# STM32F05_V2.net
KiCad netlist of a schematic drawn in EAGLE
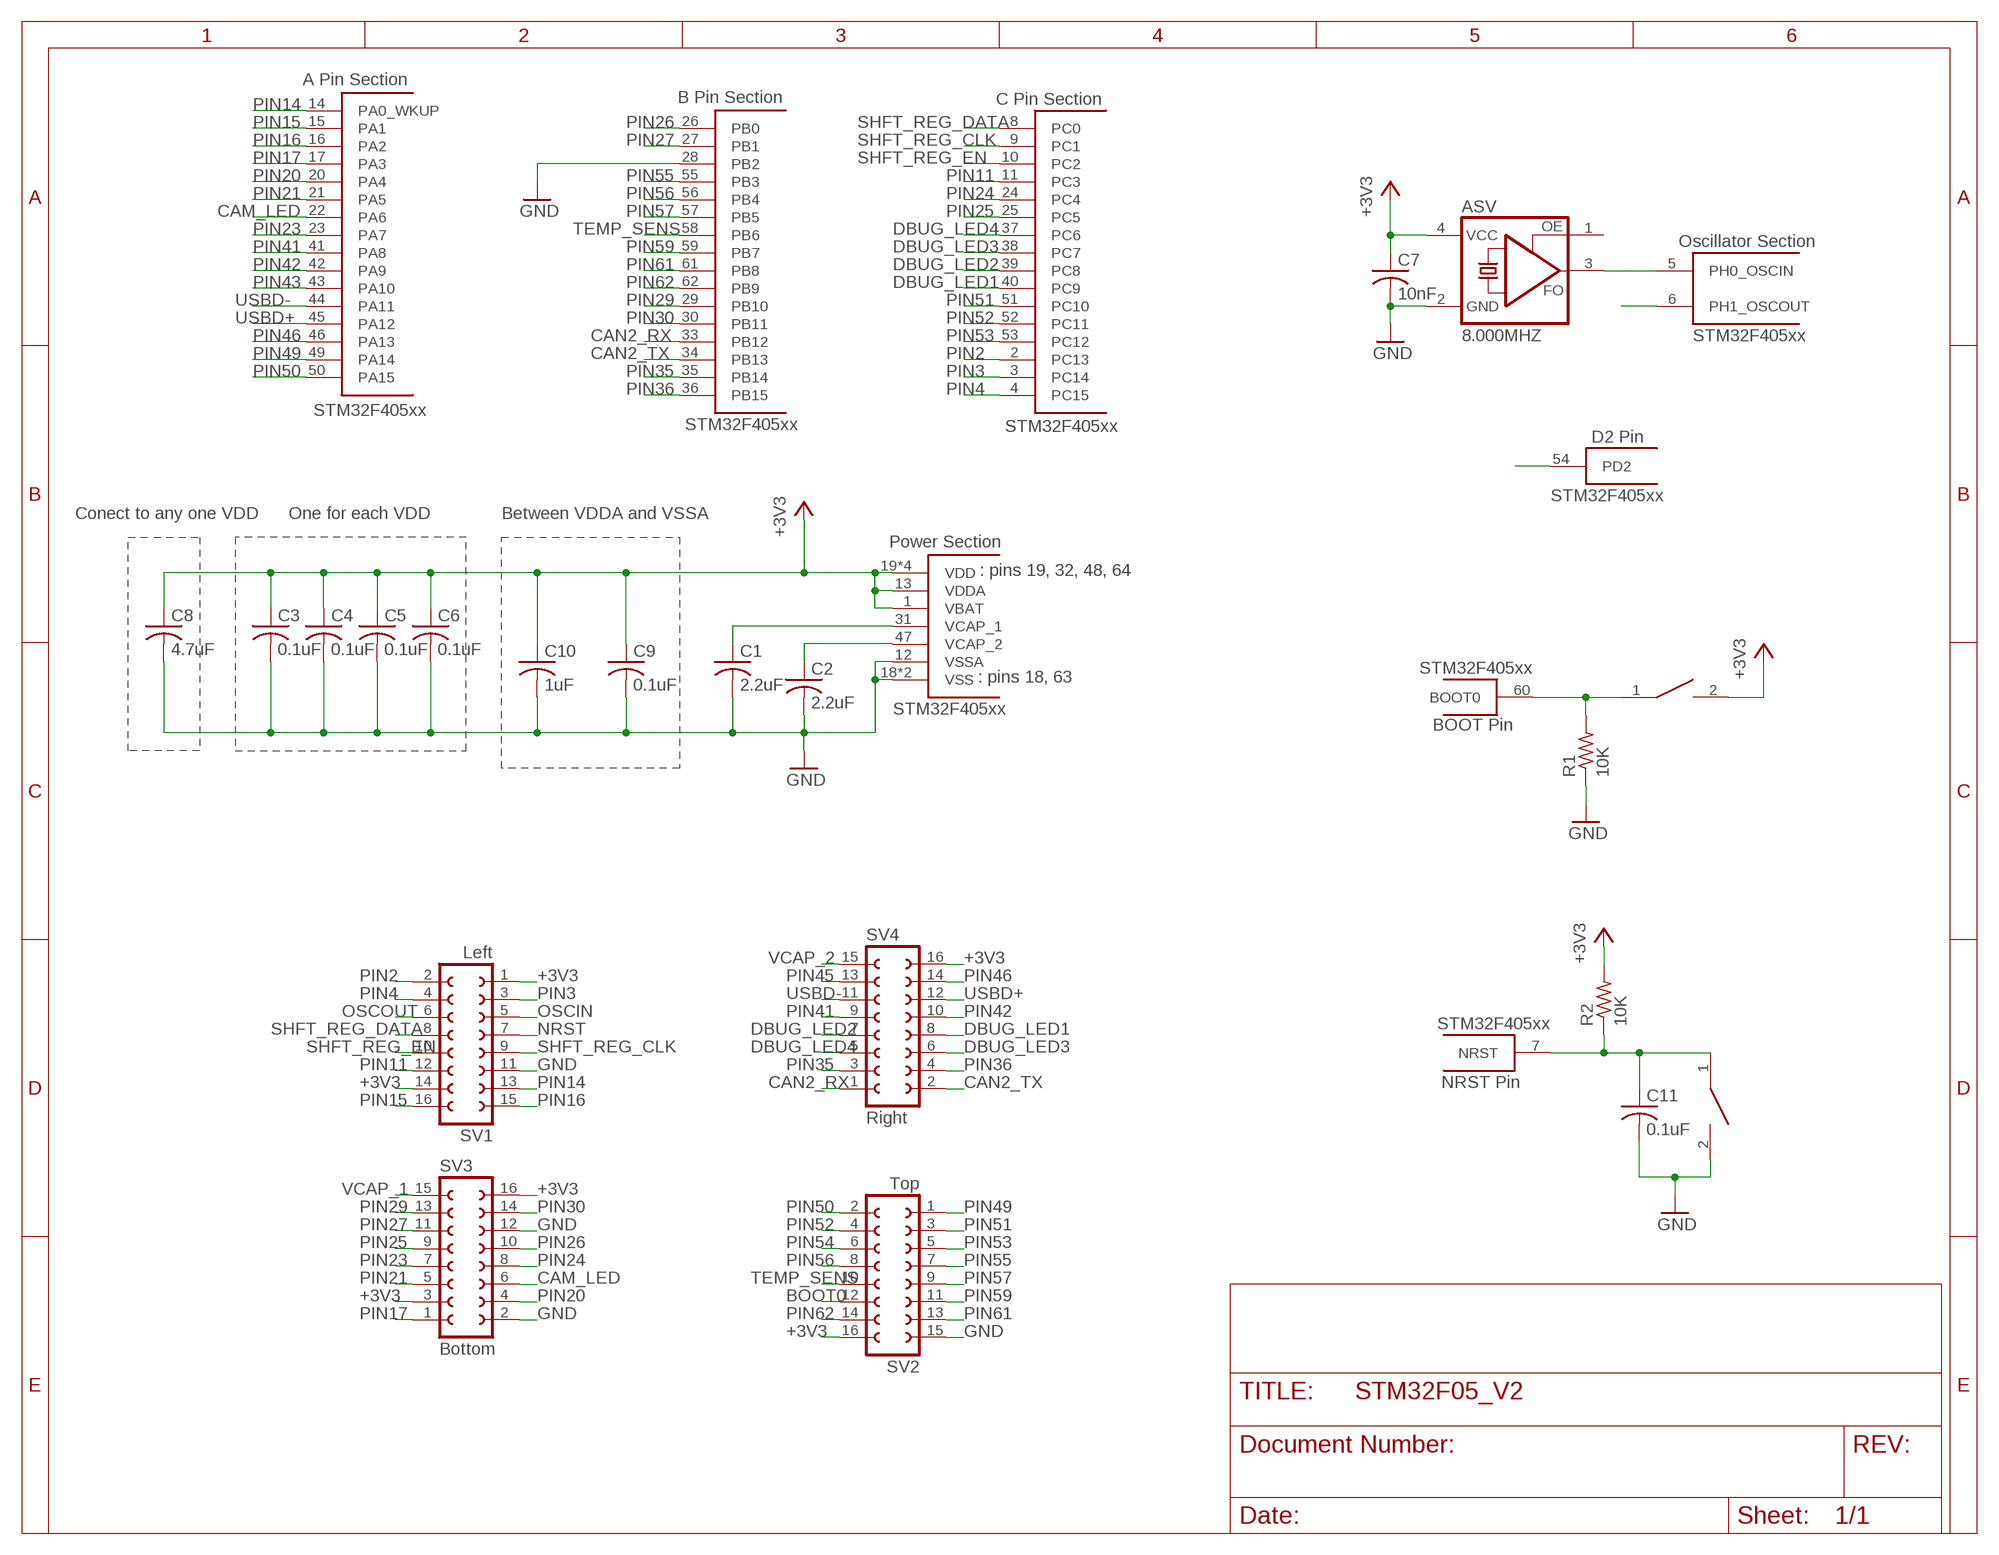
[diagram p0: schematic, sheet 1, part 1 of 2]
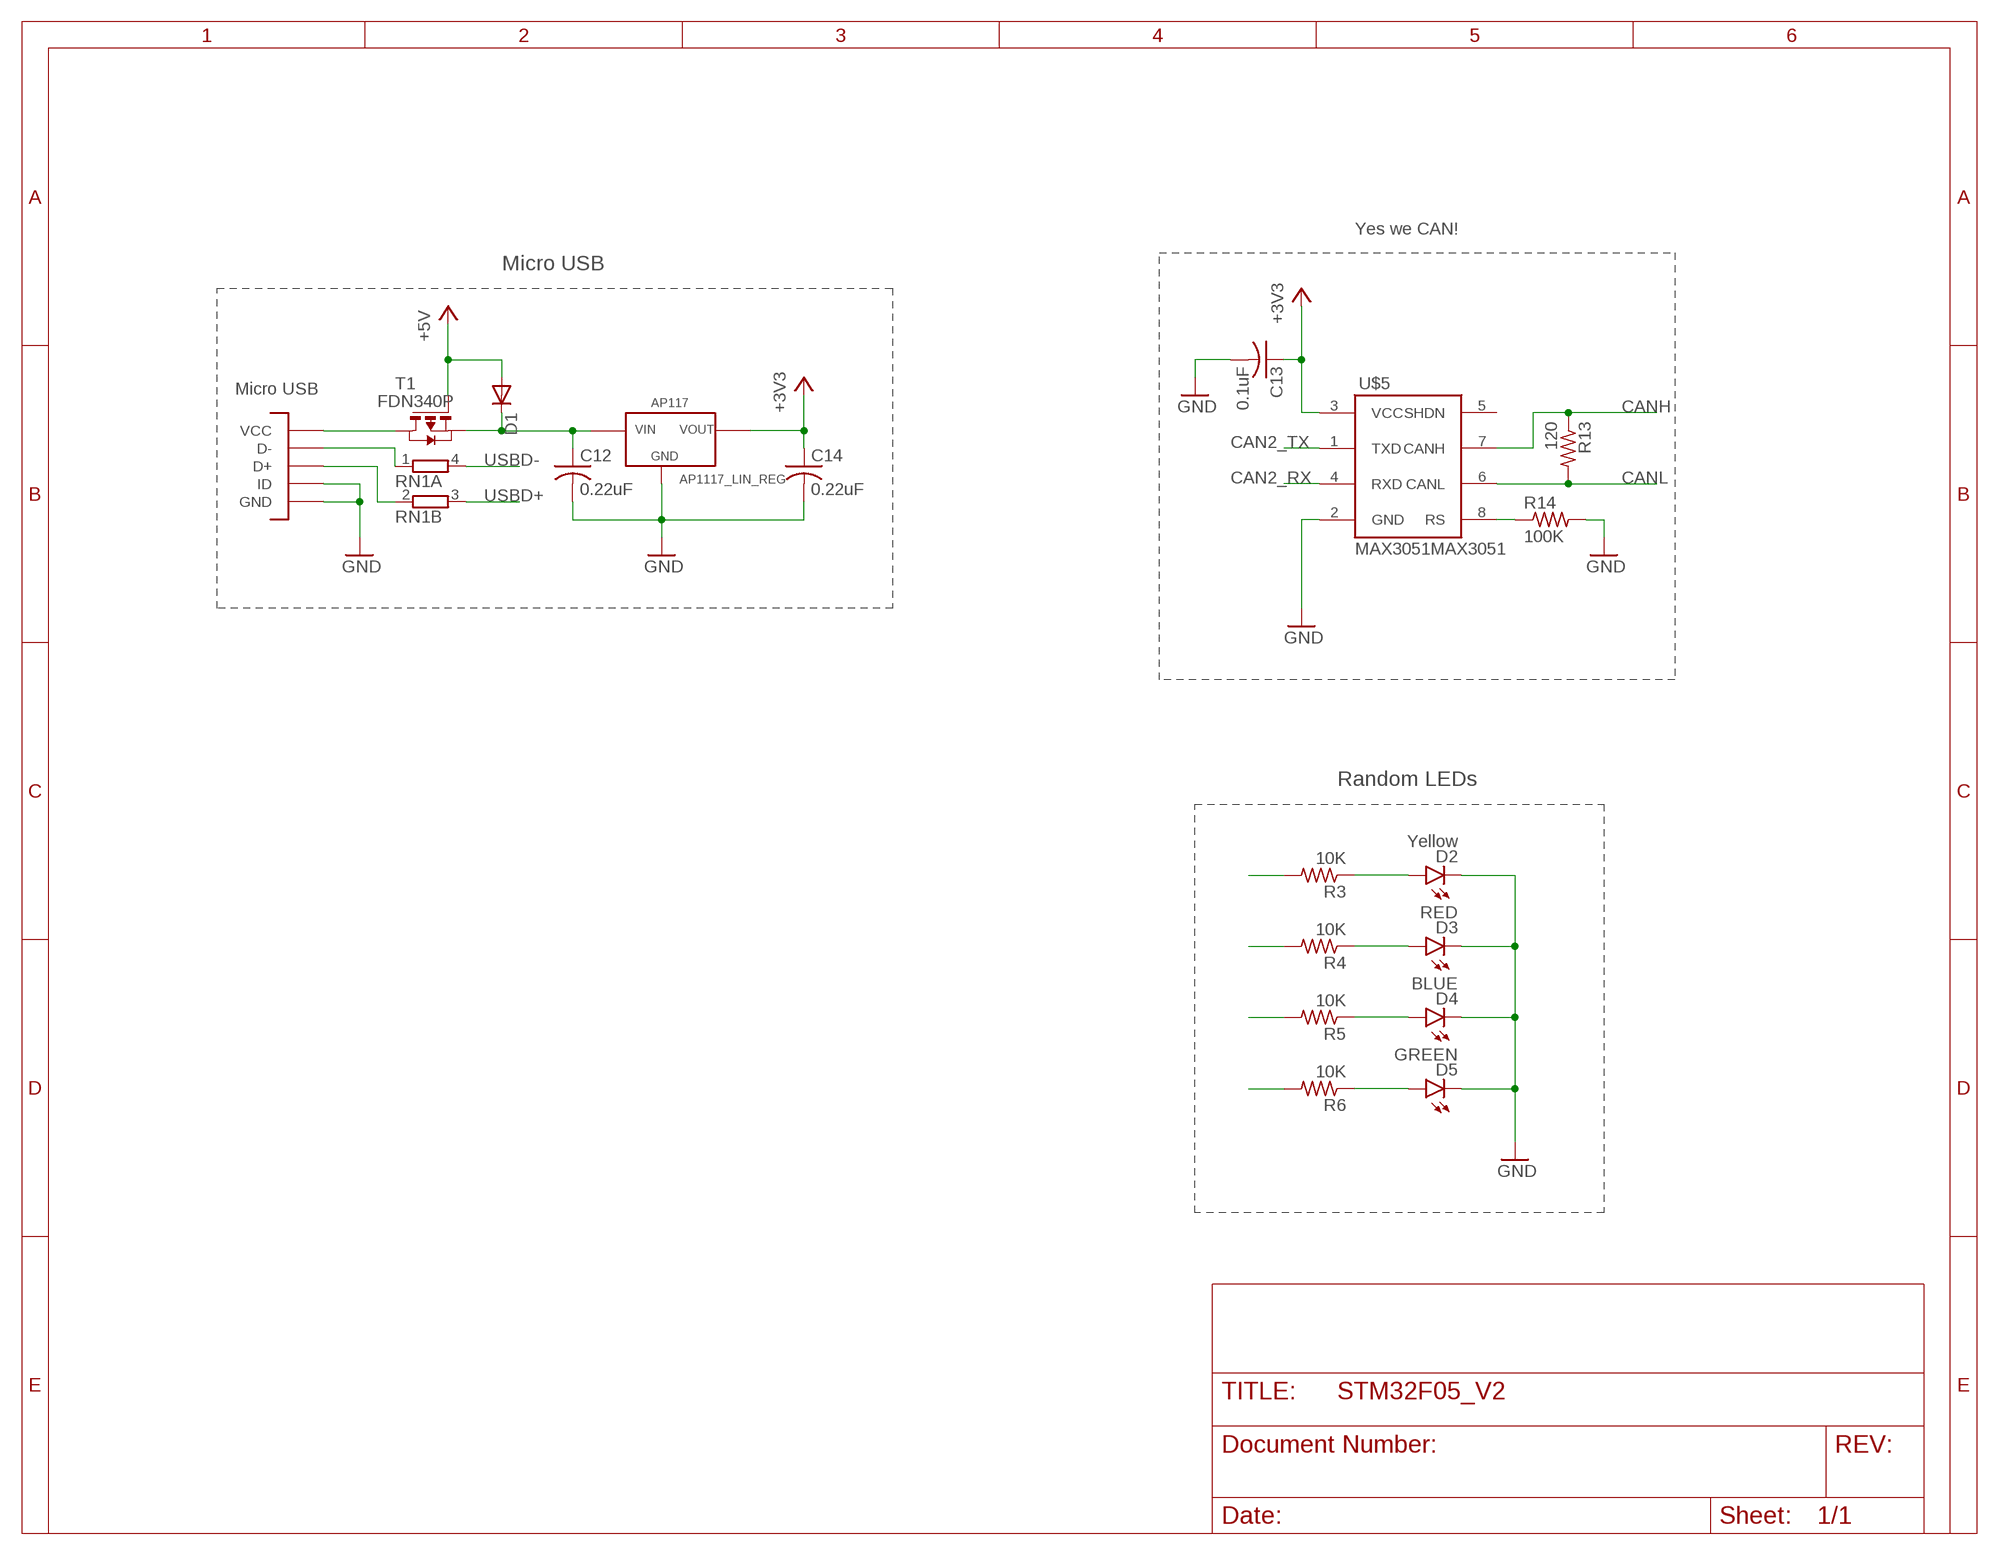
[diagram p1: schematic, sheet 1, part 2 of 2]

(export (version "E")
  (design (tool "Eeschema 10.0.6"))
  (components
    (comp (ref "ASV")
      (value "8.000MHZ")
      (footprint "eagle-import:ASF")
      (libsource (lib "eagle-import") (part "ASF"))
    )
    (comp (ref "C1")
      (value "2.2uF")
      (footprint "eagle-import:C0603")
      (libsource (lib "eagle-import") (part "C-USC0603"))
    )
    (comp (ref "C2")
      (value "2.2uF")
      (footprint "eagle-import:C0603")
      (libsource (lib "eagle-import") (part "C-USC0603"))
    )
    (comp (ref "C3")
      (value "0.1uF")
      (footprint "eagle-import:C0603")
      (libsource (lib "eagle-import") (part "C-USC0603"))
    )
    (comp (ref "C4")
      (value "0.1uF")
      (footprint "eagle-import:C0603")
      (libsource (lib "eagle-import") (part "C-USC0603"))
    )
    (comp (ref "C5")
      (value "0.1uF")
      (footprint "eagle-import:C0603")
      (libsource (lib "eagle-import") (part "C-USC0603"))
    )
    (comp (ref "C6")
      (value "0.1uF")
      (footprint "eagle-import:C0603")
      (libsource (lib "eagle-import") (part "C-USC0603"))
    )
    (comp (ref "C7")
      (value "10nF")
      (footprint "eagle-import:C0603")
      (libsource (lib "eagle-import") (part "C-USC0603"))
    )
    (comp (ref "C8")
      (value "4.7uF")
      (footprint "eagle-import:C0603")
      (libsource (lib "eagle-import") (part "C-USC0603"))
    )
    (comp (ref "C9")
      (value "0.1uF")
      (footprint "eagle-import:C0603")
      (libsource (lib "eagle-import") (part "C-USC0603"))
    )
    (comp (ref "C10")
      (value "1uF")
      (footprint "eagle-import:C0603")
      (libsource (lib "eagle-import") (part "C-USC0603"))
    )
    (comp (ref "C11")
      (value "0.1uF")
      (footprint "eagle-import:C0603")
      (libsource (lib "eagle-import") (part "C-USC0603"))
    )
    (comp (ref "C12")
      (value "0.22uF")
      (footprint "eagle-import:C0603")
      (libsource (lib "eagle-import") (part "C-USC0603"))
    )
    (comp (ref "C13")
      (value "0.1uF")
      (footprint "eagle-import:C0603")
      (libsource (lib "eagle-import") (part "C-USC0603"))
    )
    (comp (ref "C14")
      (value "0.22uF")
      (footprint "eagle-import:C0603")
      (libsource (lib "eagle-import") (part "C-USC0603"))
    )
    (comp (ref "D1")
      (value "DIODE-DO-214AC")
      (footprint "eagle-import:DO-214AC")
      (libsource (lib "eagle-import") (part "DIODE-DO-214AC"))
    )
    (comp (ref "D2")
      (value "Yellow")
      (footprint "eagle-import:LED-0603")
      (libsource (lib "eagle-import") (part "LED-YELLOW0603"))
    )
    (comp (ref "D3")
      (value "RED")
      (footprint "eagle-import:LED-0603")
      (libsource (lib "eagle-import") (part "LED-RED0603"))
    )
    (comp (ref "D4")
      (value "BLUE")
      (footprint "eagle-import:LED-0603")
      (libsource (lib "eagle-import") (part "LED-BLUE0603"))
    )
    (comp (ref "D5")
      (value "GREEN")
      (footprint "eagle-import:LED-0603")
      (libsource (lib "eagle-import") (part "LED-GREEN0603"))
    )
    (comp (ref "R1")
      (value "10K")
      (footprint "eagle-import:R0603")
      (libsource (lib "eagle-import") (part "R-US_R0603"))
    )
    (comp (ref "R2")
      (value "10K")
      (footprint "eagle-import:R0603")
      (libsource (lib "eagle-import") (part "R-US_R0603"))
    )
    (comp (ref "R3")
      (value "10K")
      (footprint "eagle-import:R0603")
      (libsource (lib "eagle-import") (part "R-US_R0603"))
    )
    (comp (ref "R4")
      (value "10K")
      (footprint "eagle-import:R0603")
      (libsource (lib "eagle-import") (part "R-US_R0603"))
    )
    (comp (ref "R5")
      (value "10K")
      (footprint "eagle-import:R0603")
      (libsource (lib "eagle-import") (part "R-US_R0603"))
    )
    (comp (ref "R6")
      (value "10K")
      (footprint "eagle-import:R0603")
      (libsource (lib "eagle-import") (part "R-US_R0603"))
    )
    (comp (ref "R13")
      (value "120")
      (footprint "eagle-import:R0603")
      (libsource (lib "eagle-import") (part "R-US_R0603"))
    )
    (comp (ref "R14")
      (value "100K")
      (footprint "eagle-import:R0603")
      (libsource (lib "eagle-import") (part "R-US_R0603"))
    )
    (comp (ref "RN1")
      (value "2R-NEXBV4V")
      (footprint "eagle-import:EXBV4V")
      (fields (field (name "MF") "Rohm Semiconductor") (field (name "MPN") "MNR12ERAPJ220"))
      (libsource (lib "eagle-import") (part "2R-NEXBV4V"))
    )
    (comp (ref "SV1")
      (value "Left")
      (footprint "eagle-import:FE08-2")
      (libsource (lib "eagle-import") (part "FE08-2"))
    )
    (comp (ref "SV2")
      (value "Top")
      (footprint "eagle-import:FE08-2")
      (libsource (lib "eagle-import") (part "FE08-2"))
    )
    (comp (ref "SV3")
      (value "Bottom")
      (footprint "eagle-import:FE08-2")
      (libsource (lib "eagle-import") (part "FE08-2"))
    )
    (comp (ref "SV4")
      (value "Right")
      (footprint "eagle-import:FE08-2")
      (libsource (lib "eagle-import") (part "FE08-2"))
    )
    (comp (ref "T1")
      (value "FDN340P")
      (footprint "eagle-import:SOT-23")
      (libsource (lib "eagle-import") (part "FDN340P"))
    )
    (comp (ref "T2")
      (value "AP1117_LIN_REG")
      (footprint "eagle-import:SOT223")
      (libsource (lib "eagle-import") (part "AP1117_LIN_REG"))
    )
    (comp (ref "U$1")
      (value "STM32F405")
      (footprint "eagle-import:LQFP64")
      (libsource (lib "eagle-import") (part "STM32F405"))
    )
    (comp (ref "U$2")
      (value "SWITCH")
      (footprint "eagle-import:SW_2512")
      (libsource (lib "eagle-import") (part "SWITCH"))
    )
    (comp (ref "U$3")
      (value "SWITCH")
      (footprint "eagle-import:SW_2512")
      (libsource (lib "eagle-import") (part "SWITCH"))
    )
    (comp (ref "U$4")
      (value "MICROUSB")
      (footprint "eagle-import:MICRO_B")
      (libsource (lib "eagle-import") (part "MICROUSB"))
    )
    (comp (ref "U$5")
      (value "MAX3051MAX3051")
      (footprint "eagle-import:SOT23-8L")
      (libsource (lib "eagle-import") (part "MAX3051MAX3051"))
    )
  )
  (nets
    (net (code "1") (name "+3V3") (class "Default")
      (node (ref "ASV") (pin "4") (pinfunction "VCC_4") (pintype "power_in"))
      (node (ref "C10") (pin "1") (pinfunction "1_1") (pintype "passive"))
      (node (ref "C13") (pin "1") (pinfunction "1_1") (pintype "passive"))
      (node (ref "C14") (pin "1") (pinfunction "1_1") (pintype "passive"))
      (node (ref "C3") (pin "1") (pinfunction "1_1") (pintype "passive"))
      (node (ref "C4") (pin "1") (pinfunction "1_1") (pintype "passive"))
      (node (ref "C5") (pin "1") (pinfunction "1_1") (pintype "passive"))
      (node (ref "C6") (pin "1") (pinfunction "1_1") (pintype "passive"))
      (node (ref "C7") (pin "1") (pinfunction "1_1") (pintype "passive"))
      (node (ref "C8") (pin "1") (pinfunction "1_1") (pintype "passive"))
      (node (ref "C9") (pin "1") (pinfunction "1_1") (pintype "passive"))
      (node (ref "R2") (pin "2") (pinfunction "2_2") (pintype "passive"))
      (node (ref "SV1") (pin "1") (pinfunction "1_1") (pintype "passive"))
      (node (ref "SV1") (pin "14") (pinfunction "14_14") (pintype "passive"))
      (node (ref "SV2") (pin "16") (pinfunction "16_16") (pintype "passive"))
      (node (ref "SV3") (pin "16") (pinfunction "16_16") (pintype "passive"))
      (node (ref "SV3") (pin "3") (pinfunction "3_3") (pintype "passive"))
      (node (ref "SV4") (pin "16") (pinfunction "16_16") (pintype "passive"))
      (node (ref "T2") (pin "TAB") (pinfunction "VOUT_TAB") (pintype "output"))
      (node (ref "T2") (pin "VOUT") (pinfunction "VOUT_VOUT") (pintype "output"))
      (node (ref "U$1") (pin "1") (pinfunction "VBAT_1") (pintype "bidirectional"))
      (node (ref "U$1") (pin "13") (pinfunction "VDDA_13") (pintype "bidirectional"))
      (node (ref "U$1") (pin "19") (pinfunction "VDD_19") (pintype "bidirectional"))
      (node (ref "U$1") (pin "32") (pinfunction "VDD_32") (pintype "bidirectional"))
      (node (ref "U$1") (pin "48") (pinfunction "VDD_48") (pintype "bidirectional"))
      (node (ref "U$1") (pin "64") (pinfunction "VDD_64") (pintype "bidirectional"))
      (node (ref "U$2") (pin "2") (pinfunction "P$2_2") (pintype "bidirectional"))
      (node (ref "U$5") (pin "3") (pinfunction "VCC_3") (pintype "bidirectional"))
    )
    (net (code "2") (name "+5V") (class "Default")
      (node (ref "D1") (pin "A") (pinfunction "A_A") (pintype "passive"))
      (node (ref "T1") (pin "3") (pinfunction "G_3") (pintype "passive"))
    )
    (net (code "3") (name "/BOOT0") (class "Default")
      (node (ref "R1") (pin "2") (pinfunction "2_2") (pintype "passive"))
      (node (ref "SV2") (pin "12") (pinfunction "12_12") (pintype "passive"))
      (node (ref "U$1") (pin "60") (pinfunction "BOOT0_60") (pintype "bidirectional"))
      (node (ref "U$2") (pin "1") (pinfunction "P$1_1") (pintype "bidirectional"))
    )
    (net (code "4") (name "/CAM_LED") (class "Default")
      (node (ref "SV3") (pin "6") (pinfunction "6_6") (pintype "passive"))
      (node (ref "U$1") (pin "22") (pinfunction "PA6_22") (pintype "bidirectional"))
    )
    (net (code "5") (name "/CAN2_RX") (class "Default")
      (node (ref "SV4") (pin "1") (pinfunction "1_1") (pintype "passive"))
      (node (ref "U$1") (pin "33") (pinfunction "PB12_33") (pintype "bidirectional"))
      (node (ref "U$5") (pin "4") (pinfunction "RXD_4") (pintype "bidirectional"))
    )
    (net (code "6") (name "/CAN2_TX") (class "Default")
      (node (ref "SV4") (pin "2") (pinfunction "2_2") (pintype "passive"))
      (node (ref "U$1") (pin "34") (pinfunction "PB13_34") (pintype "bidirectional"))
      (node (ref "U$5") (pin "1") (pinfunction "TXD_1") (pintype "bidirectional"))
    )
    (net (code "7") (name "/CANH") (class "Default")
      (node (ref "R13") (pin "1") (pinfunction "1_1") (pintype "passive"))
      (node (ref "U$5") (pin "7") (pinfunction "CANH_7") (pintype "bidirectional"))
    )
    (net (code "8") (name "/CANL") (class "Default")
      (node (ref "R13") (pin "2") (pinfunction "2_2") (pintype "passive"))
      (node (ref "U$5") (pin "6") (pinfunction "CANL_6") (pintype "bidirectional"))
    )
    (net (code "9") (name "/DBUG_LED1") (class "Default")
      (node (ref "R3") (pin "2") (pinfunction "2_2") (pintype "passive"))
      (node (ref "SV4") (pin "8") (pinfunction "8_8") (pintype "passive"))
      (node (ref "U$1") (pin "40") (pinfunction "PC9_40") (pintype "bidirectional"))
    )
    (net (code "10") (name "/DBUG_LED2") (class "Default")
      (node (ref "R4") (pin "2") (pinfunction "2_2") (pintype "passive"))
      (node (ref "SV4") (pin "7") (pinfunction "7_7") (pintype "passive"))
      (node (ref "U$1") (pin "39") (pinfunction "PC8_39") (pintype "bidirectional"))
    )
    (net (code "11") (name "/DBUG_LED3") (class "Default")
      (node (ref "R5") (pin "2") (pinfunction "2_2") (pintype "passive"))
      (node (ref "SV4") (pin "6") (pinfunction "6_6") (pintype "passive"))
      (node (ref "U$1") (pin "38") (pinfunction "PC7_38") (pintype "bidirectional"))
    )
    (net (code "12") (name "/DBUG_LED4") (class "Default")
      (node (ref "R6") (pin "2") (pinfunction "2_2") (pintype "passive"))
      (node (ref "SV4") (pin "5") (pinfunction "5_5") (pintype "passive"))
      (node (ref "U$1") (pin "37") (pinfunction "PC6_37") (pintype "bidirectional"))
    )
    (net (code "13") (name "/NRST") (class "Default")
      (node (ref "C11") (pin "1") (pinfunction "1_1") (pintype "passive"))
      (node (ref "R2") (pin "1") (pinfunction "1_1") (pintype "passive"))
      (node (ref "SV1") (pin "7") (pinfunction "7_7") (pintype "passive"))
      (node (ref "U$1") (pin "7") (pinfunction "NRST_7") (pintype "bidirectional"))
      (node (ref "U$3") (pin "1") (pinfunction "P$1_1") (pintype "bidirectional"))
    )
    (net (code "14") (name "/OSCIN") (class "Default")
      (node (ref "ASV") (pin "3") (pinfunction "FO_3") (pintype "output"))
      (node (ref "SV1") (pin "5") (pinfunction "5_5") (pintype "passive"))
      (node (ref "U$1") (pin "5") (pinfunction "PH0_OSCIN_5") (pintype "bidirectional"))
    )
    (net (code "15") (name "/OSCOUT") (class "Default")
      (node (ref "SV1") (pin "6") (pinfunction "6_6") (pintype "passive"))
      (node (ref "U$1") (pin "6") (pinfunction "PH1_OSCOUT_6") (pintype "bidirectional"))
    )
    (net (code "16") (name "/PIN2") (class "Default")
      (node (ref "SV1") (pin "2") (pinfunction "2_2") (pintype "passive"))
      (node (ref "U$1") (pin "2") (pinfunction "PC13_2") (pintype "bidirectional"))
    )
    (net (code "17") (name "/PIN3") (class "Default")
      (node (ref "SV1") (pin "3") (pinfunction "3_3") (pintype "passive"))
      (node (ref "U$1") (pin "3") (pinfunction "PC14_3") (pintype "bidirectional"))
    )
    (net (code "18") (name "/PIN4") (class "Default")
      (node (ref "SV1") (pin "4") (pinfunction "4_4") (pintype "passive"))
      (node (ref "U$1") (pin "4") (pinfunction "PC15_4") (pintype "bidirectional"))
    )
    (net (code "19") (name "/PIN11") (class "Default")
      (node (ref "SV1") (pin "12") (pinfunction "12_12") (pintype "passive"))
      (node (ref "U$1") (pin "11") (pinfunction "PC3_11") (pintype "bidirectional"))
    )
    (net (code "20") (name "/PIN14") (class "Default")
      (node (ref "SV1") (pin "13") (pinfunction "13_13") (pintype "passive"))
      (node (ref "U$1") (pin "14") (pinfunction "PA0_WKUP_14") (pintype "bidirectional"))
    )
    (net (code "21") (name "/PIN15") (class "Default")
      (node (ref "SV1") (pin "16") (pinfunction "16_16") (pintype "passive"))
      (node (ref "U$1") (pin "15") (pinfunction "PA1_15") (pintype "bidirectional"))
    )
    (net (code "22") (name "/PIN16") (class "Default")
      (node (ref "SV1") (pin "15") (pinfunction "15_15") (pintype "passive"))
      (node (ref "U$1") (pin "16") (pinfunction "PA2_16") (pintype "bidirectional"))
    )
    (net (code "23") (name "/PIN17") (class "Default")
      (node (ref "SV3") (pin "1") (pinfunction "1_1") (pintype "passive"))
      (node (ref "U$1") (pin "17") (pinfunction "PA3_17") (pintype "bidirectional"))
    )
    (net (code "24") (name "/PIN20") (class "Default")
      (node (ref "SV3") (pin "4") (pinfunction "4_4") (pintype "passive"))
      (node (ref "U$1") (pin "20") (pinfunction "PA4_20") (pintype "bidirectional"))
    )
    (net (code "25") (name "/PIN21") (class "Default")
      (node (ref "SV3") (pin "5") (pinfunction "5_5") (pintype "passive"))
      (node (ref "U$1") (pin "21") (pinfunction "PA5_21") (pintype "bidirectional"))
    )
    (net (code "26") (name "/PIN23") (class "Default")
      (node (ref "SV3") (pin "7") (pinfunction "7_7") (pintype "passive"))
      (node (ref "U$1") (pin "23") (pinfunction "PA7_23") (pintype "bidirectional"))
    )
    (net (code "27") (name "/PIN24") (class "Default")
      (node (ref "SV3") (pin "8") (pinfunction "8_8") (pintype "passive"))
      (node (ref "U$1") (pin "24") (pinfunction "PC4_24") (pintype "bidirectional"))
    )
    (net (code "28") (name "/PIN25") (class "Default")
      (node (ref "SV3") (pin "9") (pinfunction "9_9") (pintype "passive"))
      (node (ref "U$1") (pin "25") (pinfunction "PC5_25") (pintype "bidirectional"))
    )
    (net (code "29") (name "/PIN26") (class "Default")
      (node (ref "SV3") (pin "10") (pinfunction "10_10") (pintype "passive"))
      (node (ref "U$1") (pin "26") (pinfunction "PB0_26") (pintype "bidirectional"))
    )
    (net (code "30") (name "/PIN27") (class "Default")
      (node (ref "SV3") (pin "11") (pinfunction "11_11") (pintype "passive"))
      (node (ref "U$1") (pin "27") (pinfunction "PB1_27") (pintype "bidirectional"))
    )
    (net (code "31") (name "/PIN29") (class "Default")
      (node (ref "SV3") (pin "13") (pinfunction "13_13") (pintype "passive"))
      (node (ref "U$1") (pin "29") (pinfunction "PB10_29") (pintype "bidirectional"))
    )
    (net (code "32") (name "/PIN30") (class "Default")
      (node (ref "SV3") (pin "14") (pinfunction "14_14") (pintype "passive"))
      (node (ref "U$1") (pin "30") (pinfunction "PB11_30") (pintype "bidirectional"))
    )
    (net (code "33") (name "/PIN35") (class "Default")
      (node (ref "SV4") (pin "3") (pinfunction "3_3") (pintype "passive"))
      (node (ref "U$1") (pin "35") (pinfunction "PB14_35") (pintype "bidirectional"))
    )
    (net (code "34") (name "/PIN36") (class "Default")
      (node (ref "SV4") (pin "4") (pinfunction "4_4") (pintype "passive"))
      (node (ref "U$1") (pin "36") (pinfunction "PB15_36") (pintype "bidirectional"))
    )
    (net (code "35") (name "/PIN41") (class "Default")
      (node (ref "SV4") (pin "9") (pinfunction "9_9") (pintype "passive"))
      (node (ref "U$1") (pin "41") (pinfunction "PA8_41") (pintype "bidirectional"))
    )
    (net (code "36") (name "/PIN42") (class "Default")
      (node (ref "SV4") (pin "10") (pinfunction "10_10") (pintype "passive"))
      (node (ref "U$1") (pin "42") (pinfunction "PA9_42") (pintype "bidirectional"))
    )
    (net (code "37") (name "/PIN43") (class "Default")
      (node (ref "U$1") (pin "43") (pinfunction "PA10_43") (pintype "bidirectional"))
    )
    (net (code "38") (name "/PIN45") (class "Default")
      (node (ref "SV4") (pin "13") (pinfunction "13_13") (pintype "passive"))
    )
    (net (code "39") (name "/PIN46") (class "Default")
      (node (ref "SV4") (pin "14") (pinfunction "14_14") (pintype "passive"))
      (node (ref "U$1") (pin "46") (pinfunction "PA13_46") (pintype "bidirectional"))
    )
    (net (code "40") (name "/PIN49") (class "Default")
      (node (ref "SV2") (pin "1") (pinfunction "1_1") (pintype "passive"))
      (node (ref "U$1") (pin "49") (pinfunction "PA14_49") (pintype "bidirectional"))
    )
    (net (code "41") (name "/PIN50") (class "Default")
      (node (ref "SV2") (pin "2") (pinfunction "2_2") (pintype "passive"))
      (node (ref "U$1") (pin "50") (pinfunction "PA15_50") (pintype "bidirectional"))
    )
    (net (code "42") (name "/PIN51") (class "Default")
      (node (ref "SV2") (pin "3") (pinfunction "3_3") (pintype "passive"))
      (node (ref "U$1") (pin "51") (pinfunction "PC10_51") (pintype "bidirectional"))
    )
    (net (code "43") (name "/PIN52") (class "Default")
      (node (ref "SV2") (pin "4") (pinfunction "4_4") (pintype "passive"))
      (node (ref "U$1") (pin "52") (pinfunction "PC11_52") (pintype "bidirectional"))
    )
    (net (code "44") (name "/PIN53") (class "Default")
      (node (ref "SV2") (pin "5") (pinfunction "5_5") (pintype "passive"))
      (node (ref "U$1") (pin "53") (pinfunction "PC12_53") (pintype "bidirectional"))
    )
    (net (code "45") (name "/PIN54") (class "Default")
      (node (ref "SV2") (pin "6") (pinfunction "6_6") (pintype "passive"))
      (node (ref "U$1") (pin "54") (pinfunction "PD2_54") (pintype "bidirectional"))
    )
    (net (code "46") (name "/PIN55") (class "Default")
      (node (ref "SV2") (pin "7") (pinfunction "7_7") (pintype "passive"))
      (node (ref "U$1") (pin "55") (pinfunction "PB3_55") (pintype "bidirectional"))
    )
    (net (code "47") (name "/PIN56") (class "Default")
      (node (ref "SV2") (pin "8") (pinfunction "8_8") (pintype "passive"))
      (node (ref "U$1") (pin "56") (pinfunction "PB4_56") (pintype "bidirectional"))
    )
    (net (code "48") (name "/PIN57") (class "Default")
      (node (ref "SV2") (pin "9") (pinfunction "9_9") (pintype "passive"))
      (node (ref "U$1") (pin "57") (pinfunction "PB5_57") (pintype "bidirectional"))
    )
    (net (code "49") (name "/PIN59") (class "Default")
      (node (ref "SV2") (pin "11") (pinfunction "11_11") (pintype "passive"))
      (node (ref "U$1") (pin "59") (pinfunction "PB7_59") (pintype "bidirectional"))
    )
    (net (code "50") (name "/PIN61") (class "Default")
      (node (ref "SV2") (pin "13") (pinfunction "13_13") (pintype "passive"))
      (node (ref "U$1") (pin "61") (pinfunction "PB8_61") (pintype "bidirectional"))
    )
    (net (code "51") (name "/PIN62") (class "Default")
      (node (ref "SV2") (pin "14") (pinfunction "14_14") (pintype "passive"))
      (node (ref "U$1") (pin "62") (pinfunction "PB9_62") (pintype "bidirectional"))
    )
    (net (code "52") (name "/SHFT_REG_CLK") (class "Default")
      (node (ref "SV1") (pin "9") (pinfunction "9_9") (pintype "passive"))
      (node (ref "U$1") (pin "9") (pinfunction "PC1_9") (pintype "bidirectional"))
    )
    (net (code "53") (name "/SHFT_REG_DATA") (class "Default")
      (node (ref "SV1") (pin "8") (pinfunction "8_8") (pintype "passive"))
      (node (ref "U$1") (pin "8") (pinfunction "PC0_8") (pintype "bidirectional"))
    )
    (net (code "54") (name "/SHFT_REG_EN") (class "Default")
      (node (ref "SV1") (pin "10") (pinfunction "10_10") (pintype "passive"))
      (node (ref "U$1") (pin "10") (pinfunction "PC2_10") (pintype "bidirectional"))
    )
    (net (code "55") (name "/TEMP_SENS") (class "Default")
      (node (ref "SV2") (pin "10") (pinfunction "10_10") (pintype "passive"))
      (node (ref "U$1") (pin "58") (pinfunction "PB6_58") (pintype "bidirectional"))
    )
    (net (code "56") (name "/USBD+") (class "Default")
      (node (ref "RN1") (pin "3") (pinfunction "2_3") (pintype "passive"))
      (node (ref "SV4") (pin "12") (pinfunction "12_12") (pintype "passive"))
      (node (ref "U$1") (pin "45") (pinfunction "PA12_45") (pintype "bidirectional"))
    )
    (net (code "57") (name "/USBD-") (class "Default")
      (node (ref "RN1") (pin "4") (pinfunction "2_4") (pintype "passive"))
      (node (ref "SV4") (pin "11") (pinfunction "11_11") (pintype "passive"))
      (node (ref "U$1") (pin "44") (pinfunction "PA11_44") (pintype "bidirectional"))
    )
    (net (code "58") (name "/VCAP_1") (class "Default")
      (node (ref "C1") (pin "1") (pinfunction "1_1") (pintype "passive"))
      (node (ref "SV3") (pin "15") (pinfunction "15_15") (pintype "passive"))
      (node (ref "U$1") (pin "31") (pinfunction "VCAP_1_31") (pintype "bidirectional"))
    )
    (net (code "59") (name "/VCAP_2") (class "Default")
      (node (ref "C2") (pin "1") (pinfunction "1_1") (pintype "passive"))
      (node (ref "SV4") (pin "15") (pinfunction "15_15") (pintype "passive"))
      (node (ref "U$1") (pin "47") (pinfunction "VCAP_2_47") (pintype "bidirectional"))
    )
    (net (code "60") (name "GND") (class "Default")
      (node (ref "ASV") (pin "2") (pinfunction "GND_2") (pintype "power_in"))
      (node (ref "C1") (pin "2") (pinfunction "2_2") (pintype "passive"))
      (node (ref "C10") (pin "2") (pinfunction "2_2") (pintype "passive"))
      (node (ref "C11") (pin "2") (pinfunction "2_2") (pintype "passive"))
      (node (ref "C12") (pin "2") (pinfunction "2_2") (pintype "passive"))
      (node (ref "C13") (pin "2") (pinfunction "2_2") (pintype "passive"))
      (node (ref "C14") (pin "2") (pinfunction "2_2") (pintype "passive"))
      (node (ref "C2") (pin "2") (pinfunction "2_2") (pintype "passive"))
      (node (ref "C3") (pin "2") (pinfunction "2_2") (pintype "passive"))
      (node (ref "C4") (pin "2") (pinfunction "2_2") (pintype "passive"))
      (node (ref "C5") (pin "2") (pinfunction "2_2") (pintype "passive"))
      (node (ref "C6") (pin "2") (pinfunction "2_2") (pintype "passive"))
      (node (ref "C7") (pin "2") (pinfunction "2_2") (pintype "passive"))
      (node (ref "C8") (pin "2") (pinfunction "2_2") (pintype "passive"))
      (node (ref "C9") (pin "2") (pinfunction "2_2") (pintype "passive"))
      (node (ref "D2") (pin "C") (pinfunction "C_C") (pintype "passive"))
      (node (ref "D3") (pin "C") (pinfunction "C_C") (pintype "passive"))
      (node (ref "D4") (pin "C") (pinfunction "C_C") (pintype "passive"))
      (node (ref "D5") (pin "C") (pinfunction "C_C") (pintype "passive"))
      (node (ref "R1") (pin "1") (pinfunction "1_1") (pintype "passive"))
      (node (ref "R14") (pin "2") (pinfunction "2_2") (pintype "passive"))
      (node (ref "SV1") (pin "11") (pinfunction "11_11") (pintype "passive"))
      (node (ref "SV2") (pin "15") (pinfunction "15_15") (pintype "passive"))
      (node (ref "SV3") (pin "12") (pinfunction "12_12") (pintype "passive"))
      (node (ref "SV3") (pin "2") (pinfunction "2_2") (pintype "passive"))
      (node (ref "T2") (pin "GND") (pinfunction "GND_GND") (pintype "bidirectional"))
      (node (ref "U$1") (pin "12") (pinfunction "VSSA_12") (pintype "bidirectional"))
      (node (ref "U$1") (pin "18") (pinfunction "VSS_18") (pintype "bidirectional"))
      (node (ref "U$1") (pin "28") (pinfunction "PB2_28") (pintype "bidirectional"))
      (node (ref "U$1") (pin "63") (pinfunction "VSS_63") (pintype "bidirectional"))
      (node (ref "U$3") (pin "2") (pinfunction "P$2_2") (pintype "bidirectional"))
      (node (ref "U$4") (pin "GND1") (pinfunction "GND_GND1") (pintype "bidirectional"))
      (node (ref "U$4") (pin "GND2") (pinfunction "GND_GND2") (pintype "bidirectional"))
      (node (ref "U$4") (pin "GND3") (pinfunction "GND_GND3") (pintype "bidirectional"))
      (node (ref "U$4") (pin "GND4") (pinfunction "GND_GND4") (pintype "bidirectional"))
      (node (ref "U$4") (pin "GND7") (pinfunction "GND_GND7") (pintype "bidirectional"))
      (node (ref "U$4") (pin "GND8") (pinfunction "GND_GND8") (pintype "bidirectional"))
      (node (ref "U$4") (pin "P4") (pinfunction "ID_P4") (pintype "bidirectional"))
      (node (ref "U$4") (pin "P5") (pinfunction "GND_P5") (pintype "bidirectional"))
      (node (ref "U$5") (pin "2") (pinfunction "GND_2") (pintype "bidirectional"))
    )
    (net (code "61") (name "Net-(D2-PadA)") (class "Default")
      (node (ref "D2") (pin "A") (pinfunction "A_A") (pintype "passive"))
      (node (ref "R3") (pin "1") (pinfunction "1_1") (pintype "passive"))
    )
    (net (code "62") (name "Net-(D3-PadA)") (class "Default")
      (node (ref "D3") (pin "A") (pinfunction "A_A") (pintype "passive"))
      (node (ref "R4") (pin "1") (pinfunction "1_1") (pintype "passive"))
    )
    (net (code "63") (name "Net-(D4-PadA)") (class "Default")
      (node (ref "D4") (pin "A") (pinfunction "A_A") (pintype "passive"))
      (node (ref "R5") (pin "1") (pinfunction "1_1") (pintype "passive"))
    )
    (net (code "64") (name "Net-(D5-PadA)") (class "Default")
      (node (ref "D5") (pin "A") (pinfunction "A_A") (pintype "passive"))
      (node (ref "R6") (pin "1") (pinfunction "1_1") (pintype "passive"))
    )
    (net (code "65") (name "Net-(RN1B-1)") (class "Default")
      (node (ref "RN1") (pin "2") (pinfunction "1_2") (pintype "passive"))
      (node (ref "U$4") (pin "P3") (pinfunction "D+_P3") (pintype "bidirectional"))
    )
    (net (code "66") (name "Net-(T1-D)") (class "Default")
      (node (ref "T1") (pin "1") (pinfunction "D_1") (pintype "passive"))
      (node (ref "U$4") (pin "P1") (pinfunction "VCC_P1") (pintype "bidirectional"))
    )
    (net (code "67") (name "Net-(T1-S)") (class "Default")
      (node (ref "C12") (pin "1") (pinfunction "1_1") (pintype "passive"))
      (node (ref "D1") (pin "C") (pinfunction "C_C") (pintype "passive"))
      (node (ref "T1") (pin "2") (pinfunction "S_2") (pintype "passive"))
      (node (ref "T2") (pin "VIN") (pinfunction "VIN_VIN") (pintype "input"))
    )
    (net (code "68") (name "Net-(U$4-D-)") (class "Default")
      (node (ref "RN1") (pin "1") (pinfunction "1_1") (pintype "passive"))
      (node (ref "U$4") (pin "P2") (pinfunction "D-_P2") (pintype "bidirectional"))
    )
    (net (code "69") (name "Net-(U$5-RS)") (class "Default")
      (node (ref "R14") (pin "1") (pinfunction "1_1") (pintype "passive"))
      (node (ref "U$5") (pin "8") (pinfunction "RS_8") (pintype "bidirectional"))
    )
    (net (code "70") (name "unconnected-(ASV-OE-Pad1)") (class "Default")
      (node (ref "ASV") (pin "1") (pinfunction "OE_1") (pintype "input"))
    )
    (net (code "71") (name "unconnected-(U$5-SHDN-Pad5)") (class "Default")
      (node (ref "U$5") (pin "5") (pinfunction "SHDN_5") (pintype "bidirectional"))
    )
  )
)
